# rapidshark-flywheel-driver-mk-1_0.net
KiCad netlist of a schematic drawn in EAGLE
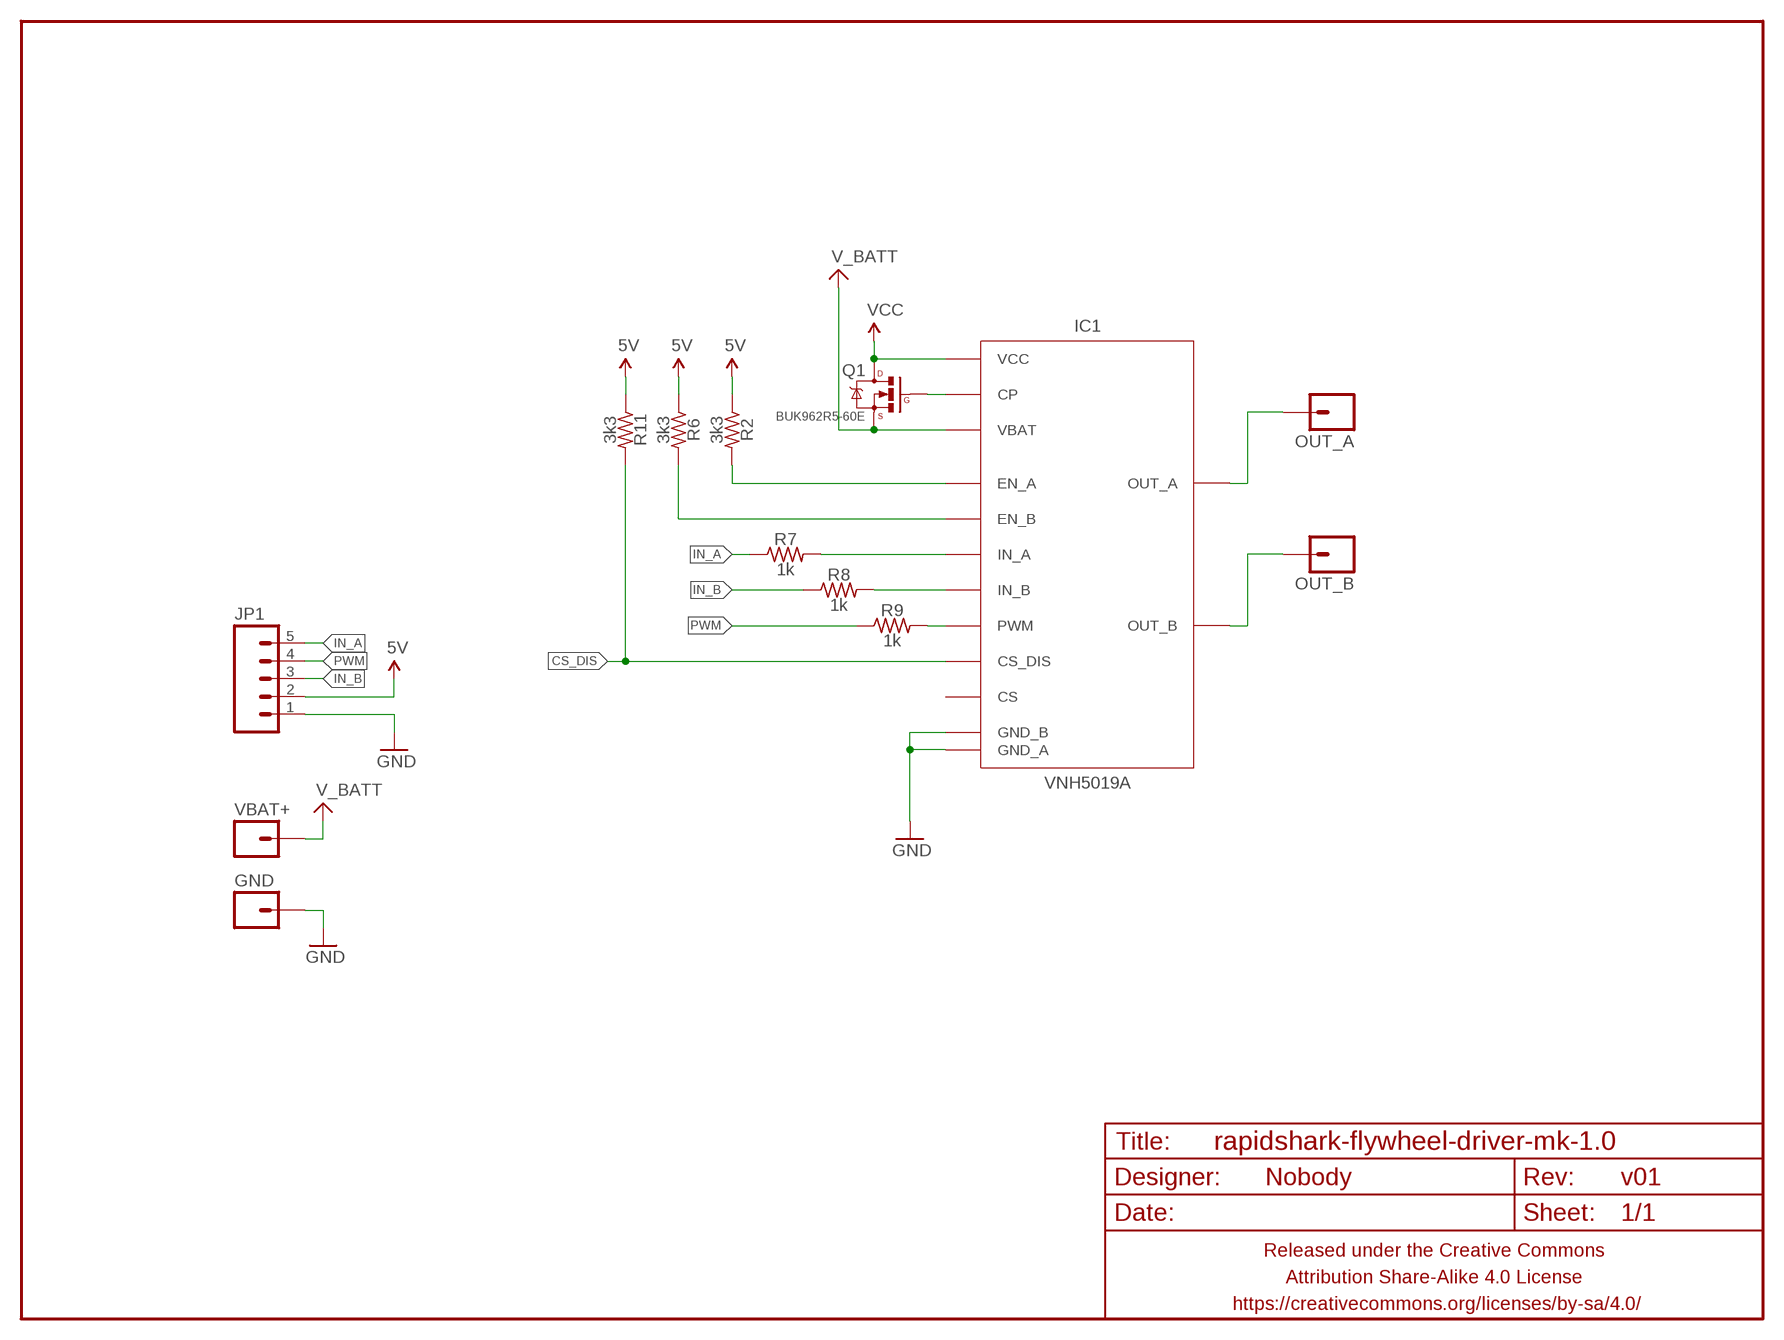
[diagram p0: schematic, sheet 1]

(export (version "E")
  (design (tool "Eeschema 10.0.6"))
  (components
    (comp (ref "FRAME1")
      (value "FRAME-LETTERNO_PACKAGE")
      (footprint "eagle-import:DUMMY")
      (fields (field (name "DESIGNER") "Nobody"))
      (libsource (lib "eagle-import") (part "FRAME-LETTERNO_PACKAGE"))
    )
    (comp (ref "GND")
      (value "M0112AWG")
      (footprint "eagle-import:1X01-12AWG")
      (libsource (lib "eagle-import") (part "M0112AWG"))
    )
    (comp (ref "IC1")
      (value "VNH5019A")
      (footprint "eagle-import:VNH5019A")
      (libsource (lib "eagle-import") (part "VNH5019A"))
    )
    (comp (ref "JP1")
      (value "M05JST-PH-RA-PTH")
      (footprint "eagle-import:JST-5-PH-RA-PTH")
      (libsource (lib "eagle-import") (part "M05JST-PH-RA-PTH"))
    )
    (comp (ref "OUT_A")
      (value "M0112AWG")
      (footprint "eagle-import:1X01-12AWG")
      (libsource (lib "eagle-import") (part "M0112AWG"))
    )
    (comp (ref "OUT_B")
      (value "M0112AWG")
      (footprint "eagle-import:1X01-12AWG")
      (libsource (lib "eagle-import") (part "M0112AWG"))
    )
    (comp (ref "Q1")
      (value "BUK962R5-60E")
      (footprint "eagle-import:SOT-669")
      (libsource (lib "eagle-import") (part "MOSFET-NCHANNELSOT-669"))
    )
    (comp (ref "R2")
      (value "3k3")
      (footprint "eagle-import:R0603")
      (libsource (lib "eagle-import") (part "RESISTORR0603"))
    )
    (comp (ref "R6")
      (value "3k3")
      (footprint "eagle-import:R0603")
      (libsource (lib "eagle-import") (part "RESISTORR0603"))
    )
    (comp (ref "R7")
      (value "1k")
      (footprint "eagle-import:R0603")
      (libsource (lib "eagle-import") (part "RESISTORR0603"))
    )
    (comp (ref "R8")
      (value "1k")
      (footprint "eagle-import:R0603")
      (libsource (lib "eagle-import") (part "RESISTORR0603"))
    )
    (comp (ref "R9")
      (value "1k")
      (footprint "eagle-import:R0603")
      (libsource (lib "eagle-import") (part "RESISTORR0603"))
    )
    (comp (ref "R11")
      (value "3k3")
      (footprint "eagle-import:R0603")
      (libsource (lib "eagle-import") (part "RESISTORR0603"))
    )
    (comp (ref "VBAT+")
      (value "M0112AWG")
      (footprint "eagle-import:1X01-12AWG")
      (libsource (lib "eagle-import") (part "M0112AWG"))
    )
  )
  (nets
    (net (code "1") (name "5V") (class "Default")
      (node (ref "JP1") (pin "2") (pinfunction "2_2") (pintype "passive"))
      (node (ref "R11") (pin "1") (pinfunction "1_1") (pintype "passive"))
      (node (ref "R2") (pin "1") (pinfunction "1_1") (pintype "passive"))
      (node (ref "R6") (pin "1") (pinfunction "1_1") (pintype "passive"))
    )
    (net (code "2") (name "CS_DIS") (class "Default")
      (node (ref "IC1") (pin "6") (pinfunction "CS_DIS_6") (pintype "bidirectional"))
      (node (ref "R11") (pin "2") (pinfunction "2_2") (pintype "passive"))
    )
    (net (code "3") (name "GND") (class "Default")
      (node (ref "GND") (pin "1") (pinfunction "1_1") (pintype "passive"))
      (node (ref "IC1") (pin "17") (pinfunction "GND_A_17") (pintype "bidirectional"))
      (node (ref "IC1") (pin "18") (pinfunction "GND_B_18") (pintype "bidirectional"))
      (node (ref "IC1") (pin "19") (pinfunction "GND_B_19") (pintype "bidirectional"))
      (node (ref "IC1") (pin "20") (pinfunction "GND_B_20") (pintype "bidirectional"))
      (node (ref "IC1") (pin "26") (pinfunction "GND_A_26") (pintype "bidirectional"))
      (node (ref "IC1") (pin "27") (pinfunction "GND_A_27") (pintype "bidirectional"))
      (node (ref "IC1") (pin "28") (pinfunction "GND_A_28") (pintype "bidirectional"))
      (node (ref "IC1") (pin "29") (pinfunction "GND_A_29") (pintype "bidirectional"))
      (node (ref "JP1") (pin "1") (pinfunction "1_1") (pintype "passive"))
    )
    (net (code "4") (name "IN_A") (class "Default")
      (node (ref "JP1") (pin "5") (pinfunction "5_5") (pintype "passive"))
      (node (ref "R7") (pin "1") (pinfunction "1_1") (pintype "passive"))
    )
    (net (code "5") (name "IN_B") (class "Default")
      (node (ref "JP1") (pin "3") (pinfunction "3_3") (pintype "passive"))
      (node (ref "R8") (pin "1") (pinfunction "1_1") (pintype "passive"))
    )
    (net (code "6") (name "Net-(IC1-CP)") (class "Default")
      (node (ref "IC1") (pin "11") (pinfunction "CP_11") (pintype "bidirectional"))
      (node (ref "Q1") (pin "4") (pinfunction "G_4") (pintype "passive"))
    )
    (net (code "7") (name "Net-(IC1-EN_A)") (class "Default")
      (node (ref "IC1") (pin "5") (pinfunction "EN_A_5") (pintype "bidirectional"))
      (node (ref "R2") (pin "2") (pinfunction "2_2") (pintype "passive"))
    )
    (net (code "8") (name "Net-(IC1-EN_B)") (class "Default")
      (node (ref "IC1") (pin "9") (pinfunction "EN_B_9") (pintype "bidirectional"))
      (node (ref "R6") (pin "2") (pinfunction "2_2") (pintype "passive"))
    )
    (net (code "9") (name "Net-(IC1-IN_A)") (class "Default")
      (node (ref "IC1") (pin "4") (pinfunction "IN_A_4") (pintype "bidirectional"))
      (node (ref "R7") (pin "2") (pinfunction "2_2") (pintype "passive"))
    )
    (net (code "10") (name "Net-(IC1-IN_B)") (class "Default")
      (node (ref "IC1") (pin "10") (pinfunction "IN_B_10") (pintype "bidirectional"))
      (node (ref "R8") (pin "2") (pinfunction "2_2") (pintype "passive"))
    )
    (net (code "11") (name "Net-(IC1-OUT_A-Pad1)") (class "Default")
      (node (ref "IC1") (pin "1") (pinfunction "OUT_A_1") (pintype "bidirectional"))
      (node (ref "IC1") (pin "24") (pinfunction "OUT_A_24") (pintype "bidirectional"))
      (node (ref "IC1") (pin "25") (pinfunction "OUT_A_25") (pintype "bidirectional"))
      (node (ref "IC1") (pin "30") (pinfunction "OUT_A_30") (pintype "bidirectional"))
      (node (ref "IC1") (pin "HS2") (pinfunction "OUT_A_HS2") (pintype "bidirectional"))
      (node (ref "OUT_A") (pin "1") (pinfunction "1_1") (pintype "passive"))
    )
    (net (code "12") (name "Net-(IC1-OUT_B-Pad15)") (class "Default")
      (node (ref "IC1") (pin "15") (pinfunction "OUT_B_15") (pintype "bidirectional"))
      (node (ref "IC1") (pin "16") (pinfunction "OUT_B_16") (pintype "bidirectional"))
      (node (ref "IC1") (pin "21") (pinfunction "OUT_B_21") (pintype "bidirectional"))
      (node (ref "IC1") (pin "22") (pinfunction "OUT_B_22") (pintype "bidirectional"))
      (node (ref "IC1") (pin "HS3") (pinfunction "OUT_B_HS3") (pintype "bidirectional"))
      (node (ref "OUT_B") (pin "1") (pinfunction "1_1") (pintype "passive"))
    )
    (net (code "13") (name "Net-(IC1-PWM)") (class "Default")
      (node (ref "IC1") (pin "7") (pinfunction "PWM_7") (pintype "bidirectional"))
      (node (ref "R9") (pin "2") (pinfunction "2_2") (pintype "passive"))
    )
    (net (code "14") (name "PWM") (class "Default")
      (node (ref "JP1") (pin "4") (pinfunction "4_4") (pintype "passive"))
      (node (ref "R9") (pin "1") (pinfunction "1_1") (pintype "passive"))
    )
    (net (code "15") (name "VCC") (class "Default")
      (node (ref "IC1") (pin "13") (pinfunction "VCC_13") (pintype "bidirectional"))
      (node (ref "IC1") (pin "14") (pinfunction "VCC_14") (pintype "bidirectional"))
      (node (ref "IC1") (pin "2") (pinfunction "VCC_2") (pintype "bidirectional"))
      (node (ref "IC1") (pin "23") (pinfunction "VCC_23") (pintype "bidirectional"))
      (node (ref "IC1") (pin "3") (pinfunction "VCC_3") (pintype "bidirectional"))
      (node (ref "IC1") (pin "HS1") (pinfunction "VCC_HS1") (pintype "bidirectional"))
      (node (ref "Q1") (pin "5") (pinfunction "D_5") (pintype "passive"))
    )
    (net (code "16") (name "V_BATT") (class "Default")
      (node (ref "IC1") (pin "12") (pinfunction "VBAT_12") (pintype "bidirectional"))
      (node (ref "Q1") (pin "1") (pinfunction "S_1") (pintype "passive"))
      (node (ref "Q1") (pin "2") (pinfunction "S_2") (pintype "passive"))
      (node (ref "Q1") (pin "3") (pinfunction "S_3") (pintype "passive"))
      (node (ref "VBAT+") (pin "1") (pinfunction "1_1") (pintype "passive"))
    )
    (net (code "17") (name "unconnected-(IC1-CS-Pad8)") (class "Default")
      (node (ref "IC1") (pin "8") (pinfunction "CS_8") (pintype "bidirectional"))
    )
  )
)
